# R3Mkr12F_MB.net
KiCad netlist of a schematic drawn in EAGLE
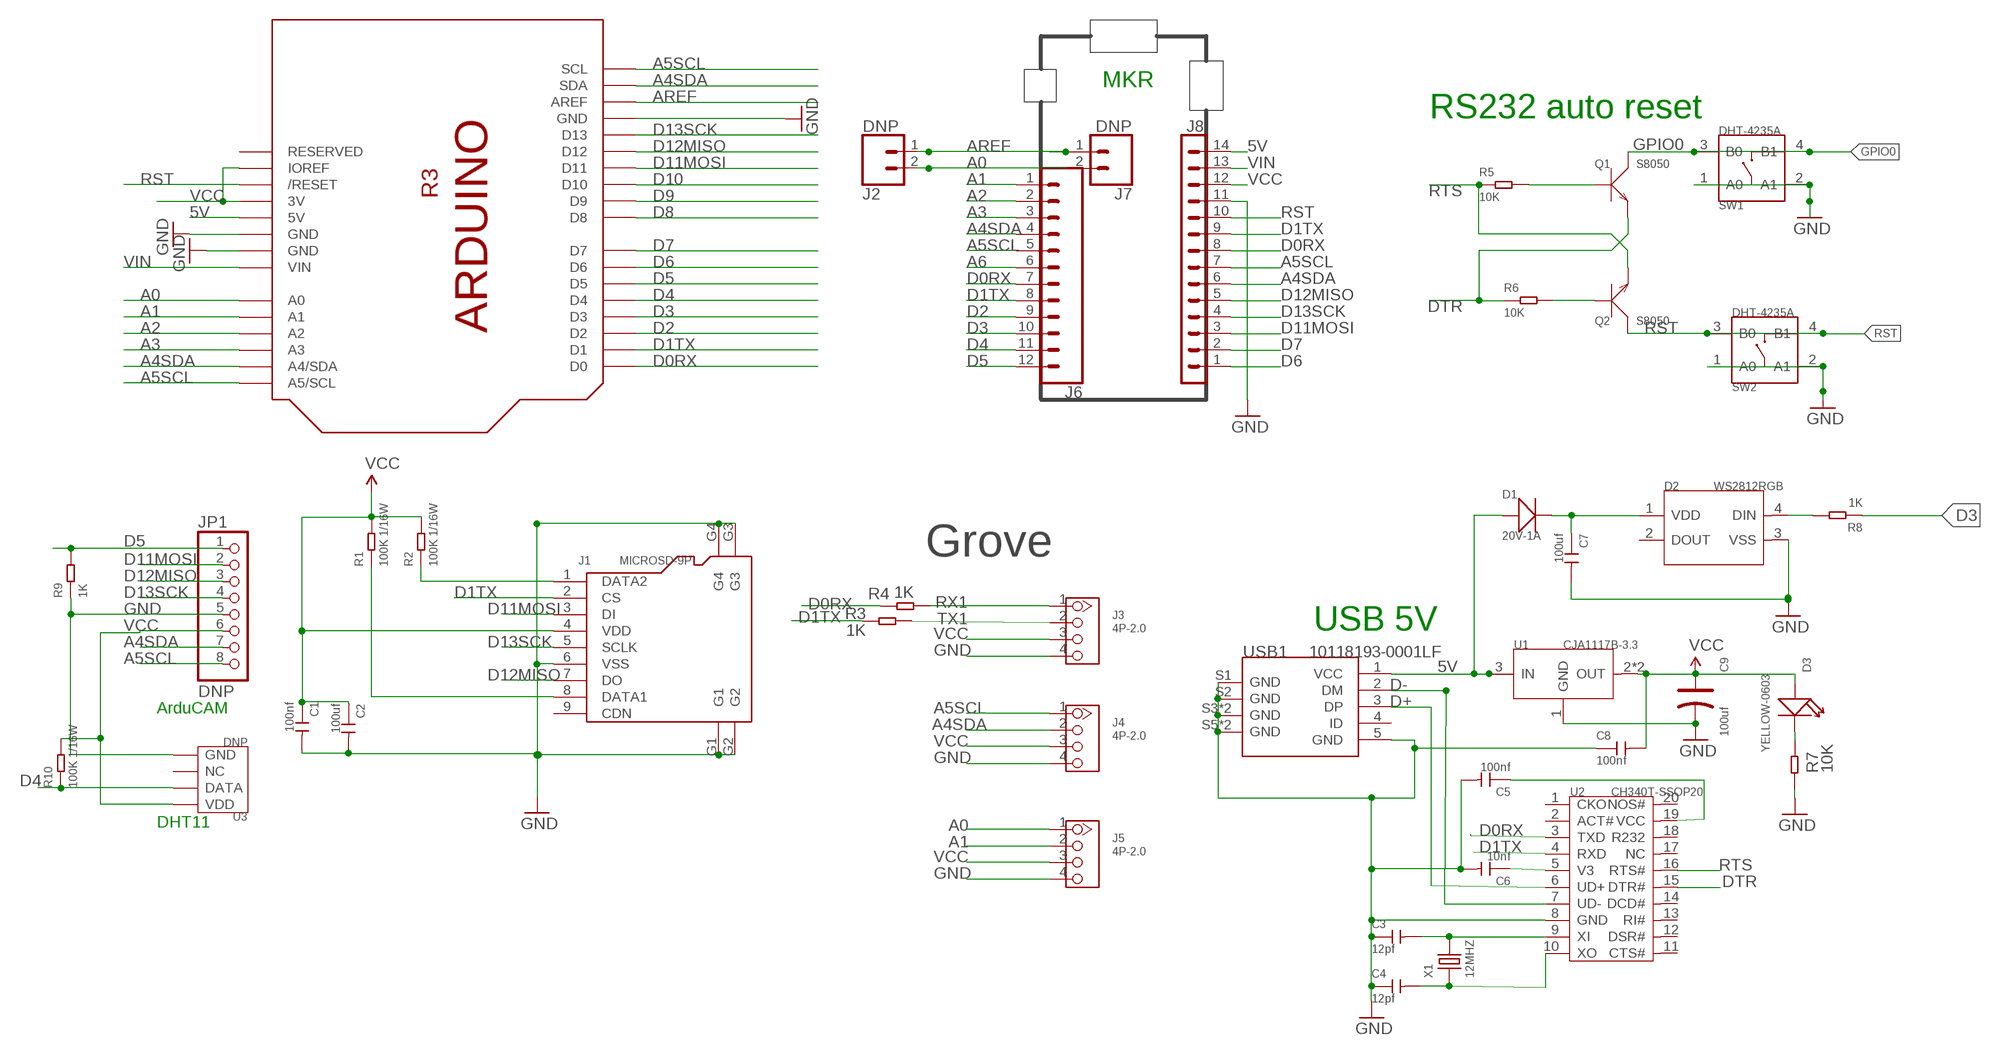
[diagram p0: schematic, sheet 1]

(export (version "E")
  (design (tool "Eeschema 10.0.6"))
  (components
    (comp (ref "C1")
      (value "100nf")
      (footprint "eagle-import:C0603")
      (fields (field (name "MPN") "CC0603KRX7R9BB104"))
      (libsource (lib "eagle-import") (part "CERAMIC-100NF-50V-10%-X7R(0603)"))
    )
    (comp (ref "C2")
      (value "100uf")
      (footprint "eagle-import:C1206")
      (fields (field (name "MPN") "GRM31CR60J107ME39L"))
      (libsource (lib "eagle-import") (part "CERAMIC-100UF-6.3V-20%-X5R(1206)"))
    )
    (comp (ref "C3")
      (value "12pf")
      (footprint "eagle-import:C0402")
      (fields (field (name "MPN") "CC0402JRNPO9BN120"))
      (libsource (lib "eagle-import") (part "CERAMIC-12PF-50V-5%-NPO(0402)"))
    )
    (comp (ref "C4")
      (value "12pf")
      (footprint "eagle-import:C0402")
      (fields (field (name "MPN") "CC0402JRNPO9BN120"))
      (libsource (lib "eagle-import") (part "CERAMIC-12PF-50V-5%-NPO(0402)"))
    )
    (comp (ref "C5")
      (value "100nf")
      (footprint "eagle-import:C0603")
      (fields (field (name "MPN") "CC0603KRX7R9BB104"))
      (libsource (lib "eagle-import") (part "CERAMIC-100NF-50V-10%-X7R(0603)"))
    )
    (comp (ref "C6")
      (value "10nf")
      (footprint "eagle-import:C0603")
      (fields (field (name "MPN") "CC0603KRX7R9BB103"))
      (libsource (lib "eagle-import") (part "CERAMIC-10NF-50V-10%-X7R(0603)"))
    )
    (comp (ref "C7")
      (value "100uf")
      (footprint "eagle-import:C1206")
      (fields (field (name "MPN") "GRM31CR60J107ME39L"))
      (libsource (lib "eagle-import") (part "CERAMIC-100UF-6.3V-20%-X5R(1206)"))
    )
    (comp (ref "C8")
      (value "100nf")
      (footprint "eagle-import:C0603")
      (fields (field (name "MPN") "CC0603KRX7R9BB104"))
      (libsource (lib "eagle-import") (part "CERAMIC-100NF-50V-10%-X7R(0603)"))
    )
    (comp (ref "C9")
      (value "100uf")
      (footprint "eagle-import:AVX-B")
      (fields (field (name "MPN") "TAJB107M010#NJ"))
      (libsource (lib "eagle-import") (part "TANTALUM-SMD-100UF-10V(AVX-B)"))
    )
    (comp (ref "D1")
      (value "20V-1A")
      (footprint "eagle-import:SOD-123")
      (fields (field (name "MPN") "B5819W"))
      (libsource (lib "eagle-import") (part "SMD-DIODE-SCHOTTKY-20V-1A(SOD-123)"))
    )
    (comp (ref "D2")
      (value "WS2812RGB")
      (footprint "eagle-import:LED4-SMD-5050")
      (libsource (lib "eagle-import") (part "SMD-RGB-LED-4P'WS2812B'"))
    )
    (comp (ref "D3")
      (value "YELLOW-0603")
      (footprint "eagle-import:LED-0603")
      (fields (field (name "MPN") "19-217-Y5C-AM1N1VY-3T"))
      (libsource (lib "eagle-import") (part "SMD-LED-CLEAR-YELLOW(0603)"))
    )
    (comp (ref "J1")
      (value "MICROSD-9P")
      (footprint "eagle-import:MICRO-SD9+4P-SMD-16.1X14.5X1.85MM")
      (libsource (lib "eagle-import") (part "MICRO-SD-CARD-HOLDER-9P"))
    )
    (comp (ref "J2")
      (value "DNP")
      (footprint "eagle-import:1X02")
      (libsource (lib "eagle-import") (part "CONN_02"))
    )
    (comp (ref "J3")
      (value "4P-2.0")
      (footprint "eagle-import:HW4-2.0")
      (libsource (lib "eagle-import") (part "GROVE-CONNECTOR-DIP(4P-2.0)"))
    )
    (comp (ref "J4")
      (value "4P-2.0")
      (footprint "eagle-import:HW4-2.0")
      (libsource (lib "eagle-import") (part "GROVE-CONNECTOR-DIP(4P-2.0)"))
    )
    (comp (ref "J5")
      (value "4P-2.0")
      (footprint "eagle-import:HW4-2.0")
      (libsource (lib "eagle-import") (part "GROVE-CONNECTOR-DIP(4P-2.0)"))
    )
    (comp (ref "J6")
      (value "CONN_12LOCK")
      (footprint "eagle-import:1X12_LOCK")
      (libsource (lib "eagle-import") (part "CONN_12LOCK"))
    )
    (comp (ref "J7")
      (value "DNP")
      (footprint "eagle-import:1X02")
      (libsource (lib "eagle-import") (part "CONN_02"))
    )
    (comp (ref "J8")
      (value "DNP")
      (footprint "eagle-import:1X14")
      (libsource (lib "eagle-import") (part "STRIP-14STD"))
    )
    (comp (ref "JP1")
      (value "DNP")
      (footprint "eagle-import:MILLER_1X08-LOCK")
      (libsource (lib "eagle-import") (part "MILLER_PINHD-1X8LOCK"))
    )
    (comp (ref "Q1")
      (value "S8050")
      (footprint "eagle-import:SOT-23")
      (libsource (lib "eagle-import") (part "SMD-TRANSISTORS-NPN-25V-500MW-S8050(SOT-23)"))
    )
    (comp (ref "Q2")
      (value "S8050")
      (footprint "eagle-import:SOT-23")
      (libsource (lib "eagle-import") (part "SMD-TRANSISTORS-NPN-25V-500MW-S8050(SOT-23)"))
    )
    (comp (ref "R1")
      (value "100K 1/16W")
      (footprint "eagle-import:R0402")
      (fields (field (name "MPN") "RC0402JR-07100KL"))
      (libsource (lib "eagle-import") (part "SMD-RES-100K-5%-1/16W(0402)"))
    )
    (comp (ref "R2")
      (value "100K 1/16W")
      (footprint "eagle-import:R0402")
      (fields (field (name "MPN") "RC0402JR-07100KL"))
      (libsource (lib "eagle-import") (part "SMD-RES-100K-5%-1/16W(0402)"))
    )
    (comp (ref "R3")
      (value "1K")
      (footprint "eagle-import:R0805")
      (fields (field (name "MPN") "RC0805JR-071KL"))
      (libsource (lib "eagle-import") (part "SMD-RES-1K-5%-1/8W(0805)"))
    )
    (comp (ref "R4")
      (value "1K")
      (footprint "eagle-import:R0805")
      (fields (field (name "MPN") "RC0805JR-071KL"))
      (libsource (lib "eagle-import") (part "SMD-RES-1K-5%-1/8W(0805)"))
    )
    (comp (ref "R5")
      (value "10K")
      (footprint "eagle-import:R0402")
      (fields (field (name "MPN") "RC0402JR-0710KL"))
      (libsource (lib "eagle-import") (part "SMD-RES-10K-5%-1/(0402)"))
    )
    (comp (ref "R6")
      (value "10K")
      (footprint "eagle-import:R0402")
      (fields (field (name "MPN") "RC0402JR-0710KL"))
      (libsource (lib "eagle-import") (part "SMD-RES-10K-5%-1/(0402)"))
    )
    (comp (ref "R7")
      (value "10K")
      (footprint "eagle-import:R0402")
      (fields (field (name "MPN") "RC0402JR-0710KL"))
      (libsource (lib "eagle-import") (part "SMD-RES-10K-5%-1/(0402)"))
    )
    (comp (ref "R8")
      (value "1K")
      (footprint "eagle-import:R0805")
      (fields (field (name "MPN") "RC0805JR-071KL"))
      (libsource (lib "eagle-import") (part "SMD-RES-1K-5%-1/8W(0805)"))
    )
    (comp (ref "R9")
      (value "1K")
      (footprint "eagle-import:R0805")
      (fields (field (name "MPN") "RC0805JR-071KL"))
      (libsource (lib "eagle-import") (part "SMD-RES-1K-5%-1/8W(0805)"))
    )
    (comp (ref "R10")
      (value "100K 1/16W")
      (footprint "eagle-import:R0402")
      (fields (field (name "MPN") "RC0402JR-07100KL"))
      (libsource (lib "eagle-import") (part "SMD-RES-100K-5%-1/16W(0402)"))
    )
    (comp (ref "SW1")
      (value "DHT-4235A")
      (footprint "eagle-import:SW4-SMD-4.2X3.2X2.5MM")
      (libsource (lib "eagle-import") (part "SMD-BUTTON-TOP-DHT-4235A(4P-4.2X3.2MM)"))
    )
    (comp (ref "SW2")
      (value "DHT-4235A")
      (footprint "eagle-import:SW4-SMD-4.2X3.2X2.5MM")
      (libsource (lib "eagle-import") (part "SMD-BUTTON-TOP-DHT-4235A(4P-4.2X3.2MM)"))
    )
    (comp (ref "U1")
      (value "CJA1117B-3.3")
      (footprint "eagle-import:SOT-89")
      (libsource (lib "eagle-import") (part "PMIC-CJ1117'SOT89'"))
    )
    (comp (ref "U2")
      (value "CH340T-SSOP20")
      (footprint "eagle-import:SSOP20-0.65-7.6X5.2MM")
      (fields (field (name "MPN") "CH340T"))
      (libsource (lib "eagle-import") (part "INTERFACE-CH340T(SSOP20)"))
    )
    (comp (ref "U3")
      (value "DNP")
      (footprint "eagle-import:SNR4-2.54-15.5X12.0X5.5MM")
      (fields (field (name "MPN") "DHT11"))
      (libsource (lib "eagle-import") (part "TEM-HUM-DHT11(4P-15.5X12.0MM)"))
    )
    (comp (ref "UNO1")
      (value "ARDUINO_R3_NOICSP_47MM")
      (footprint "eagle-import:ARDUINOR3_NOICSP_47MM")
      (libsource (lib "eagle-import") (part "ARDUINO_R3_NOICSP_47MM"))
    )
    (comp (ref "USB1")
      (value "10118193-0001LF")
      (footprint "eagle-import:MICRO-USB5+6P-SMD-0.65-B")
      (libsource (lib "eagle-import") (part "MICRO-USB-SMD-B-(10118193-0001LF)"))
    )
    (comp (ref "X1")
      (value "12MHZ")
      (footprint "eagle-import:X2-SMD-5.0X3.2X1.3MM")
      (fields (field (name "MPN") "5032/2P"))
      (libsource (lib "eagle-import") (part "SMD-CRYSTAL-12MHZ-20PF-20PPM-40R(2P-5.0X3.2MM)"))
    )
  )
  (nets
    (net (code "1") (name "/5V") (class "Default")
      (node (ref "D1") (pin "+") (pinfunction "+_+") (pintype "passive"))
      (node (ref "J8") (pin "14") (pinfunction "14_14") (pintype "passive"))
      (node (ref "U1") (pin "3") (pinfunction "IN_3") (pintype "bidirectional"))
      (node (ref "UNO1") (pin "5V") (pinfunction "5V_5V") (pintype "power_in"))
      (node (ref "USB1") (pin "1") (pinfunction "VCC_1") (pintype "bidirectional"))
    )
    (net (code "2") (name "/A0") (class "Default")
      (node (ref "J2") (pin "2") (pinfunction "2_2") (pintype "passive"))
      (node (ref "J5") (pin "1") (pinfunction "1_1") (pintype "bidirectional"))
      (node (ref "J7") (pin "2") (pinfunction "2_2") (pintype "passive"))
      (node (ref "UNO1") (pin "A0") (pinfunction "A0_A0") (pintype "bidirectional"))
    )
    (net (code "3") (name "/A1") (class "Default")
      (node (ref "J5") (pin "2") (pinfunction "2_2") (pintype "bidirectional"))
      (node (ref "J6") (pin "1") (pinfunction "1_1") (pintype "passive"))
      (node (ref "UNO1") (pin "A1") (pinfunction "A1_A1") (pintype "bidirectional"))
    )
    (net (code "4") (name "/A2") (class "Default")
      (node (ref "J6") (pin "2") (pinfunction "2_2") (pintype "passive"))
      (node (ref "UNO1") (pin "A2") (pinfunction "A2_A2") (pintype "bidirectional"))
    )
    (net (code "5") (name "/A3") (class "Default")
      (node (ref "J6") (pin "3") (pinfunction "3_3") (pintype "passive"))
      (node (ref "UNO1") (pin "A3") (pinfunction "A3_A3") (pintype "bidirectional"))
    )
    (net (code "6") (name "/A4SDA") (class "Default")
      (node (ref "J4") (pin "2") (pinfunction "2_2") (pintype "bidirectional"))
      (node (ref "J6") (pin "4") (pinfunction "4_4") (pintype "passive"))
      (node (ref "J8") (pin "6") (pinfunction "6_6") (pintype "passive"))
      (node (ref "JP1") (pin "7") (pinfunction "7_7") (pintype "passive"))
      (node (ref "UNO1") (pin "A4") (pinfunction "A4/SDA_A4") (pintype "bidirectional"))
      (node (ref "UNO1") (pin "SDA") (pinfunction "SDA_SDA") (pintype "bidirectional"))
    )
    (net (code "7") (name "/A5SCL") (class "Default")
      (node (ref "J4") (pin "1") (pinfunction "1_1") (pintype "bidirectional"))
      (node (ref "J6") (pin "5") (pinfunction "5_5") (pintype "passive"))
      (node (ref "J8") (pin "7") (pinfunction "7_7") (pintype "passive"))
      (node (ref "JP1") (pin "8") (pinfunction "8_8") (pintype "passive"))
      (node (ref "UNO1") (pin "A5") (pinfunction "A5/SCL_A5") (pintype "bidirectional"))
      (node (ref "UNO1") (pin "SCL") (pinfunction "SCL_SCL") (pintype "bidirectional"))
    )
    (net (code "8") (name "/A6") (class "Default")
      (node (ref "J6") (pin "6") (pinfunction "6_6") (pintype "passive"))
    )
    (net (code "9") (name "/AREF") (class "Default")
      (node (ref "J2") (pin "1") (pinfunction "1_1") (pintype "passive"))
      (node (ref "J7") (pin "1") (pinfunction "1_1") (pintype "passive"))
      (node (ref "UNO1") (pin "AREF") (pinfunction "AREF_AREF") (pintype "bidirectional"))
    )
    (net (code "10") (name "/D+") (class "Default")
      (node (ref "U2") (pin "6") (pinfunction "UD+_6") (pintype "bidirectional"))
      (node (ref "USB1") (pin "3") (pinfunction "DP_3") (pintype "bidirectional"))
    )
    (net (code "11") (name "/D-") (class "Default")
      (node (ref "U2") (pin "7") (pinfunction "UD-_7") (pintype "bidirectional"))
      (node (ref "USB1") (pin "2") (pinfunction "DM_2") (pintype "bidirectional"))
    )
    (net (code "12") (name "/D0RX") (class "Default")
      (node (ref "J6") (pin "7") (pinfunction "7_7") (pintype "passive"))
      (node (ref "J8") (pin "8") (pinfunction "8_8") (pintype "passive"))
      (node (ref "R4") (pin "2") (pinfunction "2_2") (pintype "passive"))
      (node (ref "U2") (pin "3") (pinfunction "TXD_3") (pintype "output"))
      (node (ref "UNO1") (pin "D0") (pinfunction "D0_D0") (pintype "bidirectional"))
    )
    (net (code "13") (name "/D1TX") (class "Default")
      (node (ref "J1") (pin "2") (pinfunction "CS_2") (pintype "bidirectional"))
      (node (ref "J6") (pin "8") (pinfunction "8_8") (pintype "passive"))
      (node (ref "J8") (pin "9") (pinfunction "9_9") (pintype "passive"))
      (node (ref "R3") (pin "2") (pinfunction "2_2") (pintype "passive"))
      (node (ref "U2") (pin "4") (pinfunction "RXD_4") (pintype "input"))
      (node (ref "UNO1") (pin "D1") (pinfunction "D1_D1") (pintype "bidirectional"))
    )
    (net (code "14") (name "/D2") (class "Default")
      (node (ref "J6") (pin "9") (pinfunction "9_9") (pintype "passive"))
      (node (ref "UNO1") (pin "D2") (pinfunction "D2_D2") (pintype "bidirectional"))
    )
    (net (code "15") (name "/D4") (class "Default")
      (node (ref "J6") (pin "11") (pinfunction "11_11") (pintype "passive"))
      (node (ref "R10") (pin "1") (pinfunction "1_1") (pintype "passive"))
      (node (ref "U3") (pin "2") (pinfunction "DATA_2") (pintype "bidirectional"))
      (node (ref "UNO1") (pin "D4") (pinfunction "D4_D4") (pintype "bidirectional"))
    )
    (net (code "16") (name "/D5") (class "Default")
      (node (ref "J6") (pin "12") (pinfunction "12_12") (pintype "passive"))
      (node (ref "JP1") (pin "1") (pinfunction "1_1") (pintype "passive"))
      (node (ref "R9") (pin "2") (pinfunction "2_2") (pintype "passive"))
      (node (ref "UNO1") (pin "D5") (pinfunction "D5_D5") (pintype "bidirectional"))
    )
    (net (code "17") (name "/D6") (class "Default")
      (node (ref "J8") (pin "1") (pinfunction "1_1") (pintype "passive"))
      (node (ref "UNO1") (pin "D6") (pinfunction "D6_D6") (pintype "bidirectional"))
    )
    (net (code "18") (name "/D7") (class "Default")
      (node (ref "J8") (pin "2") (pinfunction "2_2") (pintype "passive"))
      (node (ref "UNO1") (pin "D7") (pinfunction "D7_D7") (pintype "bidirectional"))
    )
    (net (code "19") (name "/D8") (class "Default")
      (node (ref "UNO1") (pin "D8") (pinfunction "D8_D8") (pintype "bidirectional"))
    )
    (net (code "20") (name "/D9") (class "Default")
      (node (ref "UNO1") (pin "D9") (pinfunction "D9_D9") (pintype "bidirectional"))
    )
    (net (code "21") (name "/D10") (class "Default")
      (node (ref "UNO1") (pin "D10") (pinfunction "D10_D10") (pintype "bidirectional"))
    )
    (net (code "22") (name "/D11MOSI") (class "Default")
      (node (ref "J1") (pin "3") (pinfunction "DI_3") (pintype "bidirectional"))
      (node (ref "J8") (pin "3") (pinfunction "3_3") (pintype "passive"))
      (node (ref "JP1") (pin "2") (pinfunction "2_2") (pintype "passive"))
      (node (ref "UNO1") (pin "D11") (pinfunction "D11_D11") (pintype "bidirectional"))
    )
    (net (code "23") (name "/D12MISO") (class "Default")
      (node (ref "J1") (pin "7") (pinfunction "DO_7") (pintype "bidirectional"))
      (node (ref "J8") (pin "5") (pinfunction "5_5") (pintype "passive"))
      (node (ref "JP1") (pin "3") (pinfunction "3_3") (pintype "passive"))
      (node (ref "UNO1") (pin "D12") (pinfunction "D12_D12") (pintype "bidirectional"))
    )
    (net (code "24") (name "/D13SCK") (class "Default")
      (node (ref "J1") (pin "5") (pinfunction "SCLK_5") (pintype "bidirectional"))
      (node (ref "J8") (pin "4") (pinfunction "4_4") (pintype "passive"))
      (node (ref "JP1") (pin "4") (pinfunction "4_4") (pintype "passive"))
      (node (ref "UNO1") (pin "D13") (pinfunction "D13_D13") (pintype "bidirectional"))
    )
    (net (code "25") (name "/DTR") (class "Default")
      (node (ref "Q1") (pin "2") (pinfunction "E_2") (pintype "passive"))
      (node (ref "R6") (pin "1") (pinfunction "1_1") (pintype "passive"))
      (node (ref "U2") (pin "15") (pinfunction "DTR#_15") (pintype "output"))
    )
    (net (code "26") (name "/NOS#") (class "Default")
      (node (ref "U2") (pin "20") (pinfunction "NOS#_20") (pintype "power_in"))
    )
    (net (code "27") (name "/RTS") (class "Default")
      (node (ref "Q2") (pin "2") (pinfunction "E_2") (pintype "passive"))
      (node (ref "R5") (pin "1") (pinfunction "1_1") (pintype "passive"))
      (node (ref "U2") (pin "16") (pinfunction "RTS#_16") (pintype "output"))
    )
    (net (code "28") (name "/RX1") (class "Default")
      (node (ref "J3") (pin "1") (pinfunction "1_1") (pintype "bidirectional"))
      (node (ref "R4") (pin "1") (pinfunction "1_1") (pintype "passive"))
    )
    (net (code "29") (name "/TX1") (class "Default")
      (node (ref "J3") (pin "2") (pinfunction "2_2") (pintype "bidirectional"))
      (node (ref "R3") (pin "1") (pinfunction "1_1") (pintype "passive"))
    )
    (net (code "30") (name "/VIN") (class "Default")
      (node (ref "J8") (pin "13") (pinfunction "13_13") (pintype "passive"))
      (node (ref "UNO1") (pin "VIN") (pinfunction "VIN_VIN") (pintype "power_in"))
    )
    (net (code "31") (name "D3") (class "Default")
      (node (ref "J6") (pin "10") (pinfunction "10_10") (pintype "passive"))
      (node (ref "R8") (pin "1") (pinfunction "1_1") (pintype "passive"))
      (node (ref "UNO1") (pin "D3") (pinfunction "D3_D3") (pintype "bidirectional"))
    )
    (net (code "32") (name "GND") (class "Default")
      (node (ref "C1") (pin "2") (pinfunction "2_2") (pintype "passive"))
      (node (ref "C2") (pin "2") (pinfunction "2_2") (pintype "passive"))
      (node (ref "C3") (pin "1") (pinfunction "1_1") (pintype "passive"))
      (node (ref "C4") (pin "1") (pinfunction "1_1") (pintype "passive"))
      (node (ref "C5") (pin "2") (pinfunction "2_2") (pintype "passive"))
      (node (ref "C6") (pin "2") (pinfunction "2_2") (pintype "passive"))
      (node (ref "C7") (pin "2") (pinfunction "2_2") (pintype "passive"))
      (node (ref "C8") (pin "1") (pinfunction "1_1") (pintype "passive"))
      (node (ref "C9") (pin "-") (pinfunction "-_-") (pintype "passive"))
      (node (ref "D2") (pin "3") (pinfunction "VSS_3") (pintype "bidirectional"))
      (node (ref "J1") (pin "6") (pinfunction "VSS_6") (pintype "bidirectional"))
      (node (ref "J1") (pin "G1") (pinfunction "G1_G1") (pintype "bidirectional"))
      (node (ref "J1") (pin "G2") (pinfunction "G2_G2") (pintype "bidirectional"))
      (node (ref "J1") (pin "G3") (pinfunction "G3_G3") (pintype "bidirectional"))
      (node (ref "J1") (pin "G4") (pinfunction "G4_G4") (pintype "bidirectional"))
      (node (ref "J3") (pin "4") (pinfunction "4_4") (pintype "bidirectional"))
      (node (ref "J4") (pin "4") (pinfunction "4_4") (pintype "bidirectional"))
      (node (ref "J5") (pin "4") (pinfunction "4_4") (pintype "bidirectional"))
      (node (ref "J8") (pin "11") (pinfunction "11_11") (pintype "passive"))
      (node (ref "JP1") (pin "5") (pinfunction "5_5") (pintype "passive"))
      (node (ref "R7") (pin "1") (pinfunction "1_1") (pintype "passive"))
      (node (ref "R9") (pin "1") (pinfunction "1_1") (pintype "passive"))
      (node (ref "SW1") (pin "1") (pinfunction "A0_1") (pintype "bidirectional"))
      (node (ref "SW1") (pin "2") (pinfunction "A1_2") (pintype "bidirectional"))
      (node (ref "SW2") (pin "1") (pinfunction "A0_1") (pintype "bidirectional"))
      (node (ref "SW2") (pin "2") (pinfunction "A1_2") (pintype "bidirectional"))
      (node (ref "U1") (pin "1") (pinfunction "GND_1") (pintype "bidirectional"))
      (node (ref "U2") (pin "8") (pinfunction "GND_8") (pintype "power_in"))
      (node (ref "U3") (pin "4") (pinfunction "GND_4") (pintype "power_in"))
      (node (ref "UNO1") (pin "GND") (pinfunction "GND_GND") (pintype "power_in"))
      (node (ref "UNO1") (pin "GND@1") (pinfunction "GND_GND@1") (pintype "power_in"))
      (node (ref "UNO1") (pin "GND@2") (pinfunction "GND_GND@2") (pintype "power_in"))
      (node (ref "USB1") (pin "5") (pinfunction "GND_5") (pintype "bidirectional"))
      (node (ref "USB1") (pin "S1") (pinfunction "GND_S1") (pintype "bidirectional"))
      (node (ref "USB1") (pin "S2") (pinfunction "GND_S2") (pintype "bidirectional"))
      (node (ref "USB1") (pin "S3") (pinfunction "GND_S3") (pintype "bidirectional"))
      (node (ref "USB1") (pin "S4") (pinfunction "GND_S4") (pintype "bidirectional"))
      (node (ref "USB1") (pin "S5") (pinfunction "GND_S5") (pintype "bidirectional"))
      (node (ref "USB1") (pin "S6") (pinfunction "GND_S6") (pintype "bidirectional"))
    )
    (net (code "33") (name "GPIO0") (class "Default")
      (node (ref "Q1") (pin "3") (pinfunction "C_3") (pintype "passive"))
      (node (ref "SW1") (pin "3") (pinfunction "B0_3") (pintype "bidirectional"))
      (node (ref "SW1") (pin "4") (pinfunction "B1_4") (pintype "bidirectional"))
    )
    (net (code "34") (name "Net-(D2-DIN)") (class "Default")
      (node (ref "D2") (pin "4") (pinfunction "DIN_4") (pintype "bidirectional"))
      (node (ref "R8") (pin "2") (pinfunction "2_2") (pintype "passive"))
    )
    (net (code "35") (name "Net-(D2-VDD)") (class "Default")
      (node (ref "C7") (pin "1") (pinfunction "1_1") (pintype "passive"))
      (node (ref "D1") (pin "-") (pinfunction "-_-") (pintype "passive"))
      (node (ref "D2") (pin "1") (pinfunction "VDD_1") (pintype "bidirectional"))
    )
    (net (code "36") (name "Net-(D3-Pad-)") (class "Default")
      (node (ref "D3") (pin "-") (pinfunction "-_-") (pintype "passive"))
      (node (ref "R7") (pin "2") (pinfunction "2_2") (pintype "passive"))
    )
    (net (code "37") (name "Net-(J1-DATA1)") (class "Default")
      (node (ref "J1") (pin "8") (pinfunction "DATA1_8") (pintype "bidirectional"))
      (node (ref "R1") (pin "1") (pinfunction "1_1") (pintype "passive"))
    )
    (net (code "38") (name "Net-(J1-DATA2)") (class "Default")
      (node (ref "J1") (pin "1") (pinfunction "DATA2_1") (pintype "bidirectional"))
      (node (ref "R2") (pin "1") (pinfunction "1_1") (pintype "passive"))
    )
    (net (code "39") (name "Net-(Q1-B)") (class "Default")
      (node (ref "Q1") (pin "1") (pinfunction "B_1") (pintype "passive"))
      (node (ref "R5") (pin "2") (pinfunction "2_2") (pintype "passive"))
    )
    (net (code "40") (name "Net-(Q2-B)") (class "Default")
      (node (ref "Q2") (pin "1") (pinfunction "B_1") (pintype "passive"))
      (node (ref "R6") (pin "2") (pinfunction "2_2") (pintype "passive"))
    )
    (net (code "41") (name "Net-(U2-V3)") (class "Default")
      (node (ref "C6") (pin "1") (pinfunction "1_1") (pintype "passive"))
      (node (ref "U2") (pin "5") (pinfunction "V3_5") (pintype "power_in"))
    )
    (net (code "42") (name "Net-(U2-XI)") (class "Default")
      (node (ref "C3") (pin "2") (pinfunction "2_2") (pintype "passive"))
      (node (ref "U2") (pin "9") (pinfunction "XI_9") (pintype "input"))
      (node (ref "X1") (pin "2") (pinfunction "2_2") (pintype "passive"))
    )
    (net (code "43") (name "Net-(U2-XO)") (class "Default")
      (node (ref "C4") (pin "2") (pinfunction "2_2") (pintype "passive"))
      (node (ref "U2") (pin "10") (pinfunction "XO_10") (pintype "output"))
      (node (ref "X1") (pin "1") (pinfunction "1_1") (pintype "passive"))
    )
    (net (code "44") (name "RST") (class "Default")
      (node (ref "J8") (pin "10") (pinfunction "10_10") (pintype "passive"))
      (node (ref "Q2") (pin "3") (pinfunction "C_3") (pintype "passive"))
      (node (ref "SW2") (pin "3") (pinfunction "B0_3") (pintype "bidirectional"))
      (node (ref "SW2") (pin "4") (pinfunction "B1_4") (pintype "bidirectional"))
      (node (ref "UNO1") (pin "RESET") (pinfunction "/RESET_RESET") (pintype "bidirectional"))
    )
    (net (code "45") (name "VCC") (class "Default")
      (node (ref "C1") (pin "1") (pinfunction "1_1") (pintype "passive"))
      (node (ref "C2") (pin "1") (pinfunction "1_1") (pintype "passive"))
      (node (ref "C5") (pin "1") (pinfunction "1_1") (pintype "passive"))
      (node (ref "C8") (pin "2") (pinfunction "2_2") (pintype "passive"))
      (node (ref "C9") (pin "+") (pinfunction "+_+") (pintype "passive"))
      (node (ref "D3") (pin "+") (pinfunction "+_+") (pintype "passive"))
      (node (ref "J1") (pin "4") (pinfunction "VDD_4") (pintype "bidirectional"))
      (node (ref "J3") (pin "3") (pinfunction "3_3") (pintype "bidirectional"))
      (node (ref "J4") (pin "3") (pinfunction "3_3") (pintype "bidirectional"))
      (node (ref "J5") (pin "3") (pinfunction "3_3") (pintype "bidirectional"))
      (node (ref "J8") (pin "12") (pinfunction "12_12") (pintype "passive"))
      (node (ref "JP1") (pin "6") (pinfunction "6_6") (pintype "passive"))
      (node (ref "R1") (pin "2") (pinfunction "2_2") (pintype "passive"))
      (node (ref "R10") (pin "2") (pinfunction "2_2") (pintype "passive"))
      (node (ref "R2") (pin "2") (pinfunction "2_2") (pintype "passive"))
      (node (ref "U1") (pin "2") (pinfunction "OUT_2") (pintype "bidirectional"))
      (node (ref "U1") (pin "4") (pinfunction "OUT_4") (pintype "bidirectional"))
      (node (ref "U2") (pin "19") (pinfunction "VCC_19") (pintype "power_in"))
      (node (ref "U3") (pin "1") (pinfunction "VDD_1") (pintype "power_in"))
      (node (ref "UNO1") (pin "3V") (pinfunction "3V_3V") (pintype "power_in"))
      (node (ref "UNO1") (pin "IOREF") (pinfunction "IOREF_IOREF") (pintype "output"))
    )
    (net (code "46") (name "unconnected-(D2-DOUT-Pad2)") (class "Default")
      (node (ref "D2") (pin "2") (pinfunction "DOUT_2") (pintype "bidirectional"))
    )
    (net (code "47") (name "unconnected-(J1-CDN-Pad9)") (class "Default")
      (node (ref "J1") (pin "9") (pinfunction "CDN_9") (pintype "bidirectional"))
    )
    (net (code "48") (name "unconnected-(U2-ACT#-Pad2)") (class "Default")
      (node (ref "U2") (pin "2") (pinfunction "ACT#_2") (pintype "output"))
    )
    (net (code "49") (name "unconnected-(U2-CKO-Pad1)") (class "Default")
      (node (ref "U2") (pin "1") (pinfunction "CKO_1") (pintype "output"))
    )
    (net (code "50") (name "unconnected-(U2-CTS#-Pad11)") (class "Default")
      (node (ref "U2") (pin "11") (pinfunction "CTS#_11") (pintype "input"))
    )
    (net (code "51") (name "unconnected-(U2-DCD#-Pad14)") (class "Default")
      (node (ref "U2") (pin "14") (pinfunction "DCD#_14") (pintype "input"))
    )
    (net (code "52") (name "unconnected-(U2-DSR#-Pad12)") (class "Default")
      (node (ref "U2") (pin "12") (pinfunction "DSR#_12") (pintype "input"))
    )
    (net (code "53") (name "unconnected-(U2-NC-Pad17)") (class "Default")
      (node (ref "U2") (pin "17") (pinfunction "NC_17") (pintype "no_connect"))
    )
    (net (code "54") (name "unconnected-(U2-R232-Pad18)") (class "Default")
      (node (ref "U2") (pin "18") (pinfunction "R232_18") (pintype "input"))
    )
    (net (code "55") (name "unconnected-(U2-RI#-Pad13)") (class "Default")
      (node (ref "U2") (pin "13") (pinfunction "RI#_13") (pintype "input"))
    )
    (net (code "56") (name "unconnected-(U3-NC-Pad3)") (class "Default")
      (node (ref "U3") (pin "3") (pinfunction "NC_3") (pintype "no_connect"))
    )
    (net (code "57") (name "unconnected-(UNO1-PadRESERVED)") (class "Default")
      (node (ref "UNO1") (pin "RESERVED") (pinfunction "RESERVED_RESERVED") (pintype "no_connect"))
    )
    (net (code "58") (name "unconnected-(USB1-ID-Pad4)") (class "Default")
      (node (ref "USB1") (pin "4") (pinfunction "ID_4") (pintype "bidirectional"))
    )
  )
)
